# pcb_organizer_sch.net
KiCad netlist of a schematic drawn in EAGLE
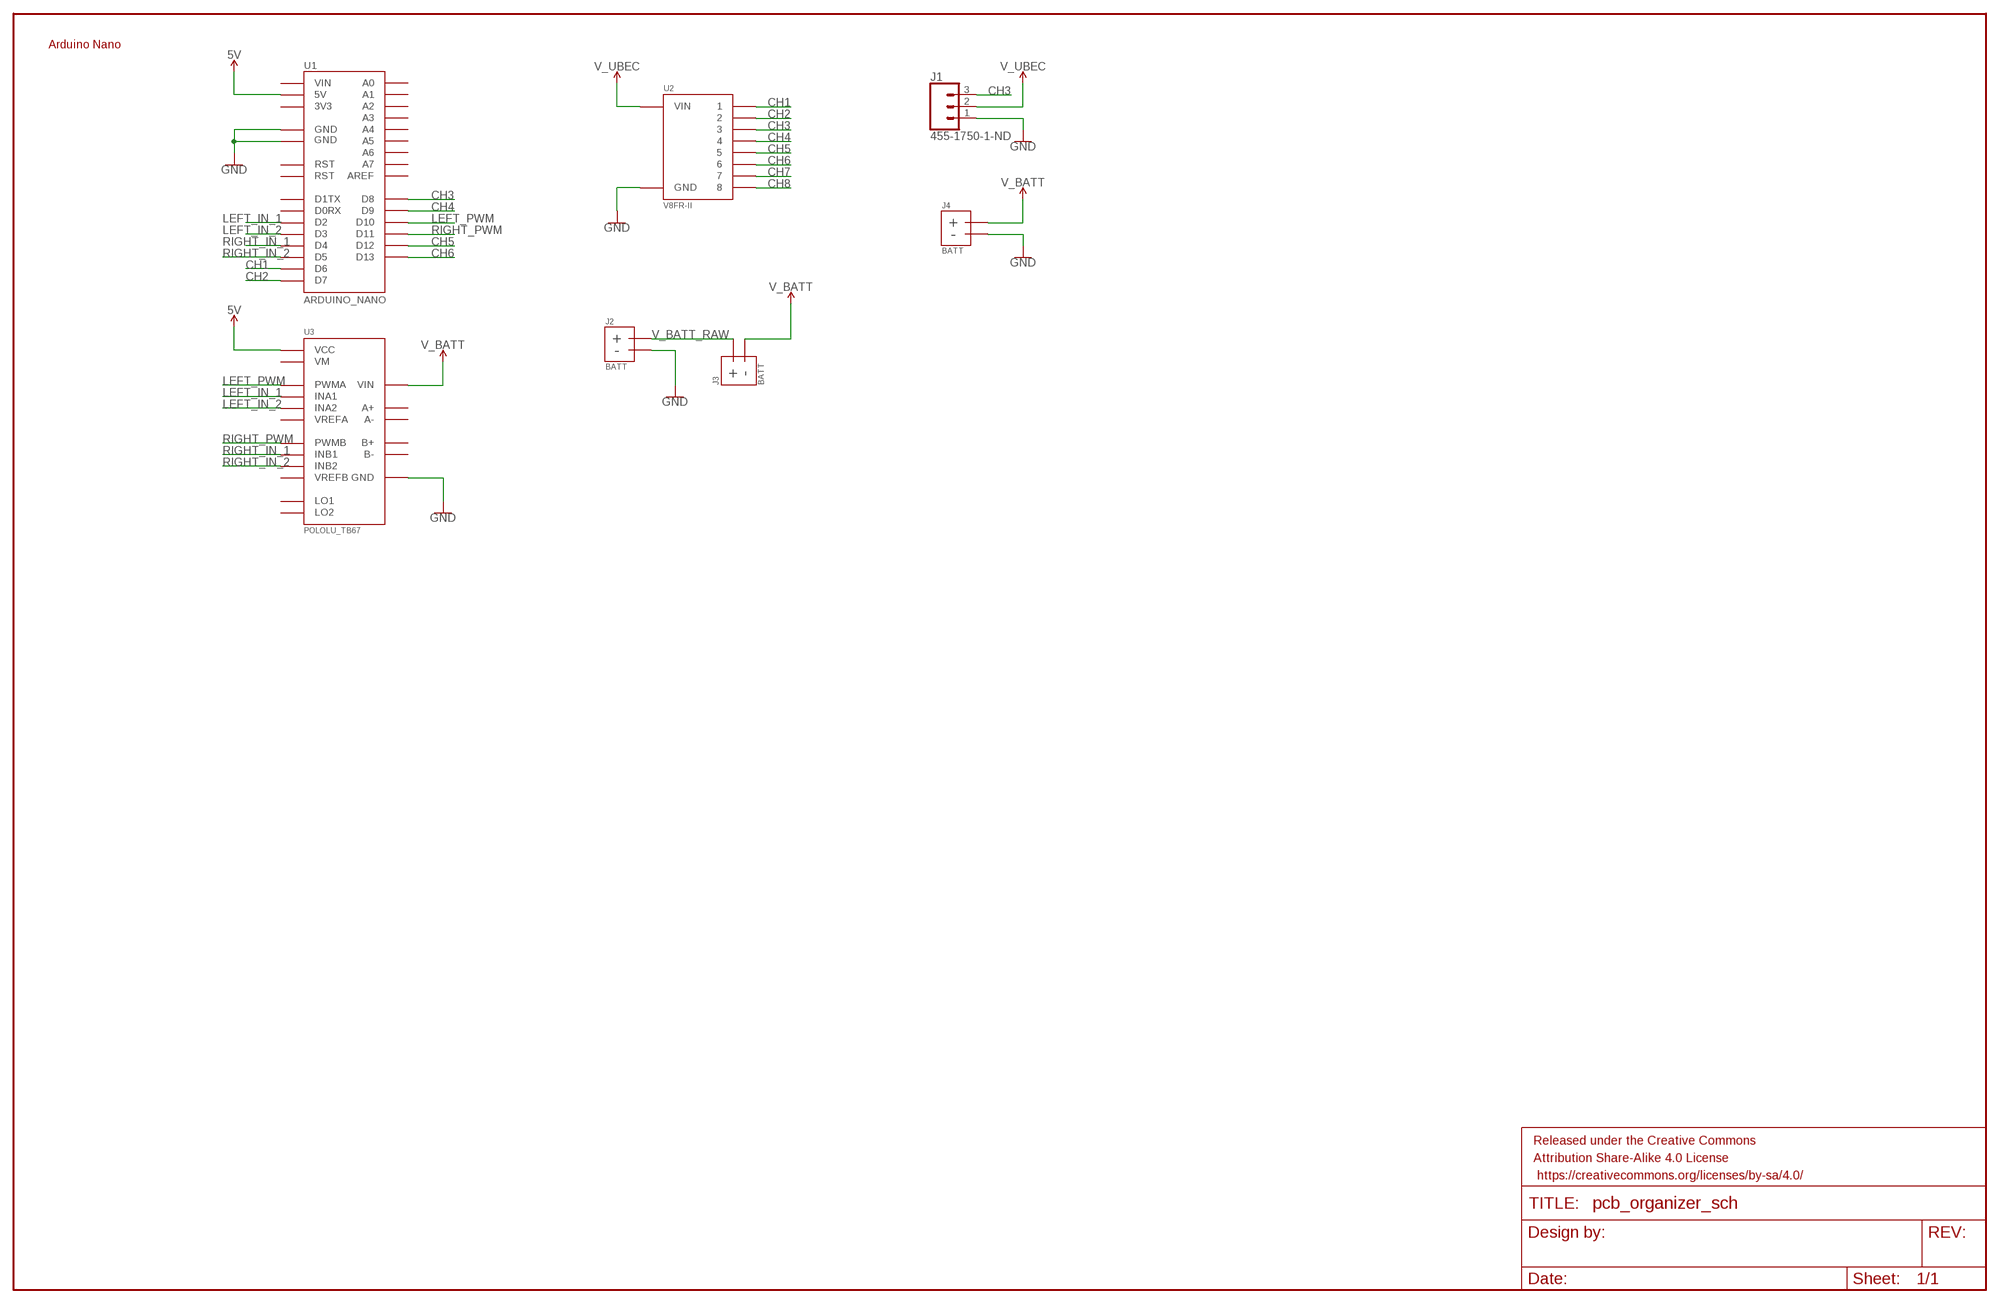
[diagram p0: schematic, sheet 1]

(export (version "E")
  (design (tool "Eeschema 10.0.6"))
  (components
    (comp (ref "FRAME1")
      (value "FRAME-LEDGER")
      (footprint "eagle-import:CREATIVE_COMMONS")
      (libsource (lib "eagle-import") (part "FRAME-LEDGER"))
    )
    (comp (ref "J1")
      (value "455-1750-1-ND")
      (footprint "eagle-import:1X03")
      (libsource (lib "eagle-import") (part "CONN_03"))
    )
    (comp (ref "J2")
      (value "BATT")
      (footprint "eagle-import:CONN_2_10AUG")
      (libsource (lib "eagle-import") (part "BATT"))
    )
    (comp (ref "J3")
      (value "BATT")
      (footprint "eagle-import:CONN_2_10AUG")
      (libsource (lib "eagle-import") (part "BATT"))
    )
    (comp (ref "J4")
      (value "BATT")
      (footprint "eagle-import:CONN_2_10AUG")
      (libsource (lib "eagle-import") (part "BATT"))
    )
    (comp (ref "U1")
      (value "ARDUINO_NANO")
      (footprint "eagle-import:ARDUINO_NANO")
      (libsource (lib "eagle-import") (part "ARDUINO_NANO"))
    )
    (comp (ref "U2")
      (value "V8FR-II")
      (footprint "eagle-import:V8FR-II")
      (libsource (lib "eagle-import") (part "V8FR-II"))
    )
    (comp (ref "U3")
      (value "POLOLU_TB67")
      (footprint "eagle-import:POLOLU_TB67")
      (libsource (lib "eagle-import") (part "POLOLU_TB67"))
    )
  )
  (nets
    (net (code "1") (name "/CH1") (class "Default")
      (node (ref "U1") (pin "D6") (pinfunction "D6_D6") (pintype "bidirectional"))
      (node (ref "U2") (pin "1") (pinfunction "1_1") (pintype "bidirectional"))
    )
    (net (code "2") (name "/CH2") (class "Default")
      (node (ref "U1") (pin "D7") (pinfunction "D7_D7") (pintype "bidirectional"))
      (node (ref "U2") (pin "2") (pinfunction "2_2") (pintype "bidirectional"))
    )
    (net (code "3") (name "/CH3") (class "Default")
      (node (ref "J1") (pin "3") (pinfunction "3_3") (pintype "passive"))
      (node (ref "U1") (pin "D8") (pinfunction "D8_D8") (pintype "bidirectional"))
      (node (ref "U2") (pin "3") (pinfunction "3_3") (pintype "bidirectional"))
    )
    (net (code "4") (name "/CH4") (class "Default")
      (node (ref "U1") (pin "D9") (pinfunction "D9_D9") (pintype "bidirectional"))
      (node (ref "U2") (pin "4") (pinfunction "4_4") (pintype "bidirectional"))
    )
    (net (code "5") (name "/CH5") (class "Default")
      (node (ref "U1") (pin "D12") (pinfunction "D12_D12") (pintype "bidirectional"))
      (node (ref "U2") (pin "5") (pinfunction "5_5") (pintype "bidirectional"))
    )
    (net (code "6") (name "/CH6") (class "Default")
      (node (ref "U1") (pin "D13") (pinfunction "D13_D13") (pintype "bidirectional"))
      (node (ref "U2") (pin "6") (pinfunction "6_6") (pintype "bidirectional"))
    )
    (net (code "7") (name "/CH7") (class "Default")
      (node (ref "U2") (pin "7") (pinfunction "7_7") (pintype "bidirectional"))
    )
    (net (code "8") (name "/CH8") (class "Default")
      (node (ref "U2") (pin "8") (pinfunction "8_8") (pintype "bidirectional"))
    )
    (net (code "9") (name "/LEFT_IN_1") (class "Default")
      (node (ref "U1") (pin "D2") (pinfunction "D2_D2") (pintype "bidirectional"))
      (node (ref "U3") (pin "INA1") (pinfunction "INA1_INA1") (pintype "bidirectional"))
    )
    (net (code "10") (name "/LEFT_IN_2") (class "Default")
      (node (ref "U1") (pin "D3") (pinfunction "D3_D3") (pintype "bidirectional"))
      (node (ref "U3") (pin "INA2") (pinfunction "INA2_INA2") (pintype "bidirectional"))
    )
    (net (code "11") (name "/LEFT_PWM") (class "Default")
      (node (ref "U1") (pin "D10") (pinfunction "D10_D10") (pintype "bidirectional"))
      (node (ref "U3") (pin "PWMA") (pinfunction "PWMA_PWMA") (pintype "bidirectional"))
    )
    (net (code "12") (name "/RIGHT_IN_1") (class "Default")
      (node (ref "U1") (pin "D4") (pinfunction "D4_D4") (pintype "bidirectional"))
      (node (ref "U3") (pin "INB1") (pinfunction "INB1_INB1") (pintype "bidirectional"))
    )
    (net (code "13") (name "/RIGHT_IN_2") (class "Default")
      (node (ref "U1") (pin "D5") (pinfunction "D5_D5") (pintype "bidirectional"))
      (node (ref "U3") (pin "INB2") (pinfunction "INB2_INB2") (pintype "bidirectional"))
    )
    (net (code "14") (name "/RIGHT_PWM") (class "Default")
      (node (ref "U1") (pin "D11") (pinfunction "D11_D11") (pintype "bidirectional"))
      (node (ref "U3") (pin "PWMB") (pinfunction "PWMB_PWMB") (pintype "bidirectional"))
    )
    (net (code "15") (name "/V_BATT_RAW") (class "Default")
      (node (ref "J2") (pin "+") (pinfunction "+_+") (pintype "power_in"))
      (node (ref "J3") (pin "+") (pinfunction "+_+") (pintype "power_in"))
    )
    (net (code "16") (name "5V") (class "Default")
      (node (ref "U1") (pin "5V") (pinfunction "5V_5V") (pintype "bidirectional"))
      (node (ref "U3") (pin "VCC") (pinfunction "VCC_VCC") (pintype "bidirectional"))
    )
    (net (code "17") (name "GND") (class "Default")
      (node (ref "J1") (pin "1") (pinfunction "1_1") (pintype "passive"))
      (node (ref "J2") (pin "-") (pinfunction "-_-") (pintype "power_in"))
      (node (ref "J4") (pin "-") (pinfunction "-_-") (pintype "power_in"))
      (node (ref "U1") (pin "GND") (pinfunction "GND_GND") (pintype "bidirectional"))
      (node (ref "U1") (pin "GND_@16") (pinfunction "GND_GND_@16") (pintype "bidirectional"))
      (node (ref "U2") (pin "GND_1") (pinfunction "GND_GND_1") (pintype "bidirectional"))
      (node (ref "U2") (pin "GND_2") (pinfunction "GND_GND_2") (pintype "bidirectional"))
      (node (ref "U2") (pin "GND_3") (pinfunction "GND_GND_3") (pintype "bidirectional"))
      (node (ref "U2") (pin "GND_4") (pinfunction "GND_GND_4") (pintype "bidirectional"))
      (node (ref "U2") (pin "GND_5") (pinfunction "GND_GND_5") (pintype "bidirectional"))
      (node (ref "U2") (pin "GND_6") (pinfunction "GND_GND_6") (pintype "bidirectional"))
      (node (ref "U2") (pin "GND_7") (pinfunction "GND_GND_7") (pintype "bidirectional"))
      (node (ref "U2") (pin "GND_8") (pinfunction "GND_GND_8") (pintype "bidirectional"))
      (node (ref "U3") (pin "GND") (pinfunction "GND_GND") (pintype "bidirectional"))
      (node (ref "U3") (pin "GND@14") (pinfunction "GND_GND@14") (pintype "bidirectional"))
      (node (ref "U3") (pin "GND@15") (pinfunction "GND_GND@15") (pintype "bidirectional"))
    )
    (net (code "18") (name "V_BATT") (class "Default")
      (node (ref "J3") (pin "-") (pinfunction "-_-") (pintype "power_in"))
      (node (ref "J4") (pin "+") (pinfunction "+_+") (pintype "power_in"))
      (node (ref "U3") (pin "VIN") (pinfunction "VIN_VIN") (pintype "bidirectional"))
    )
    (net (code "19") (name "V_UBEC") (class "Default")
      (node (ref "J1") (pin "2") (pinfunction "2_2") (pintype "passive"))
      (node (ref "U2") (pin "VIN_1") (pinfunction "VIN_VIN_1") (pintype "bidirectional"))
      (node (ref "U2") (pin "VIN_2") (pinfunction "VIN_VIN_2") (pintype "bidirectional"))
      (node (ref "U2") (pin "VIN_3") (pinfunction "VIN_VIN_3") (pintype "bidirectional"))
      (node (ref "U2") (pin "VIN_4") (pinfunction "VIN_VIN_4") (pintype "bidirectional"))
      (node (ref "U2") (pin "VIN_5") (pinfunction "VIN_VIN_5") (pintype "bidirectional"))
      (node (ref "U2") (pin "VIN_6") (pinfunction "VIN_VIN_6") (pintype "bidirectional"))
      (node (ref "U2") (pin "VIN_7") (pinfunction "VIN_VIN_7") (pintype "bidirectional"))
      (node (ref "U2") (pin "VIN_8") (pinfunction "VIN_VIN_8") (pintype "bidirectional"))
    )
    (net (code "20") (name "unconnected-(U1-Pad3V3)") (class "Default")
      (node (ref "U1") (pin "3V3") (pinfunction "3V3_3V3") (pintype "bidirectional"))
    )
    (net (code "21") (name "unconnected-(U1-PadA0)") (class "Default")
      (node (ref "U1") (pin "A0") (pinfunction "A0_A0") (pintype "bidirectional"))
    )
    (net (code "22") (name "unconnected-(U1-PadA1)") (class "Default")
      (node (ref "U1") (pin "A1") (pinfunction "A1_A1") (pintype "bidirectional"))
    )
    (net (code "23") (name "unconnected-(U1-PadA2)") (class "Default")
      (node (ref "U1") (pin "A2") (pinfunction "A2_A2") (pintype "bidirectional"))
    )
    (net (code "24") (name "unconnected-(U1-PadA3)") (class "Default")
      (node (ref "U1") (pin "A3") (pinfunction "A3_A3") (pintype "bidirectional"))
    )
    (net (code "25") (name "unconnected-(U1-PadA4)") (class "Default")
      (node (ref "U1") (pin "A4") (pinfunction "A4_A4") (pintype "bidirectional"))
    )
    (net (code "26") (name "unconnected-(U1-PadA5)") (class "Default")
      (node (ref "U1") (pin "A5") (pinfunction "A5_A5") (pintype "bidirectional"))
    )
    (net (code "27") (name "unconnected-(U1-PadA6)") (class "Default")
      (node (ref "U1") (pin "A6") (pinfunction "A6_A6") (pintype "bidirectional"))
    )
    (net (code "28") (name "unconnected-(U1-PadA7)") (class "Default")
      (node (ref "U1") (pin "A7") (pinfunction "A7_A7") (pintype "bidirectional"))
    )
    (net (code "29") (name "unconnected-(U1-PadAREF)") (class "Default")
      (node (ref "U1") (pin "AREF") (pinfunction "AREF_AREF") (pintype "bidirectional"))
    )
    (net (code "30") (name "unconnected-(U1-PadD0RX)") (class "Default")
      (node (ref "U1") (pin "D0RX") (pinfunction "D0RX_D0RX") (pintype "bidirectional"))
    )
    (net (code "31") (name "unconnected-(U1-PadD1TX)") (class "Default")
      (node (ref "U1") (pin "D1TX") (pinfunction "D1TX_D1TX") (pintype "bidirectional"))
    )
    (net (code "32") (name "unconnected-(U1-PadRST)") (class "Default")
      (node (ref "U1") (pin "RST") (pinfunction "RST_RST") (pintype "bidirectional"))
    )
    (net (code "33") (name "unconnected-(U1-PadVIN)") (class "Default")
      (node (ref "U1") (pin "VIN") (pinfunction "VIN_VIN") (pintype "bidirectional"))
    )
    (net (code "34") (name "unconnected-(U1-RST-PadRST@17)") (class "Default")
      (node (ref "U1") (pin "RST@17") (pinfunction "RST_RST@17") (pintype "bidirectional"))
    )
    (net (code "35") (name "unconnected-(U3-PadA+)") (class "Default")
      (node (ref "U3") (pin "A+") (pinfunction "A+_A+") (pintype "bidirectional"))
    )
    (net (code "36") (name "unconnected-(U3-PadA-)") (class "Default")
      (node (ref "U3") (pin "A-") (pinfunction "A-_A-") (pintype "bidirectional"))
    )
    (net (code "37") (name "unconnected-(U3-PadB+)") (class "Default")
      (node (ref "U3") (pin "B+") (pinfunction "B+_B+") (pintype "bidirectional"))
    )
    (net (code "38") (name "unconnected-(U3-PadB-)") (class "Default")
      (node (ref "U3") (pin "B-") (pinfunction "B-_B-") (pintype "bidirectional"))
    )
    (net (code "39") (name "unconnected-(U3-PadLO1)") (class "Default")
      (node (ref "U3") (pin "LO1") (pinfunction "LO1_LO1") (pintype "bidirectional"))
    )
    (net (code "40") (name "unconnected-(U3-PadLO2)") (class "Default")
      (node (ref "U3") (pin "LO2") (pinfunction "LO2_LO2") (pintype "bidirectional"))
    )
    (net (code "41") (name "unconnected-(U3-PadVM)") (class "Default")
      (node (ref "U3") (pin "VM") (pinfunction "VM_VM") (pintype "bidirectional"))
    )
    (net (code "42") (name "unconnected-(U3-PadVREFA)") (class "Default")
      (node (ref "U3") (pin "VREFA") (pinfunction "VREFA_VREFA") (pintype "bidirectional"))
    )
    (net (code "43") (name "unconnected-(U3-PadVREFB)") (class "Default")
      (node (ref "U3") (pin "VREFB") (pinfunction "VREFB_VREFB") (pintype "bidirectional"))
    )
  )
)
